# MotorDrivers.net
KiCad netlist of a schematic drawn in Altium Designer
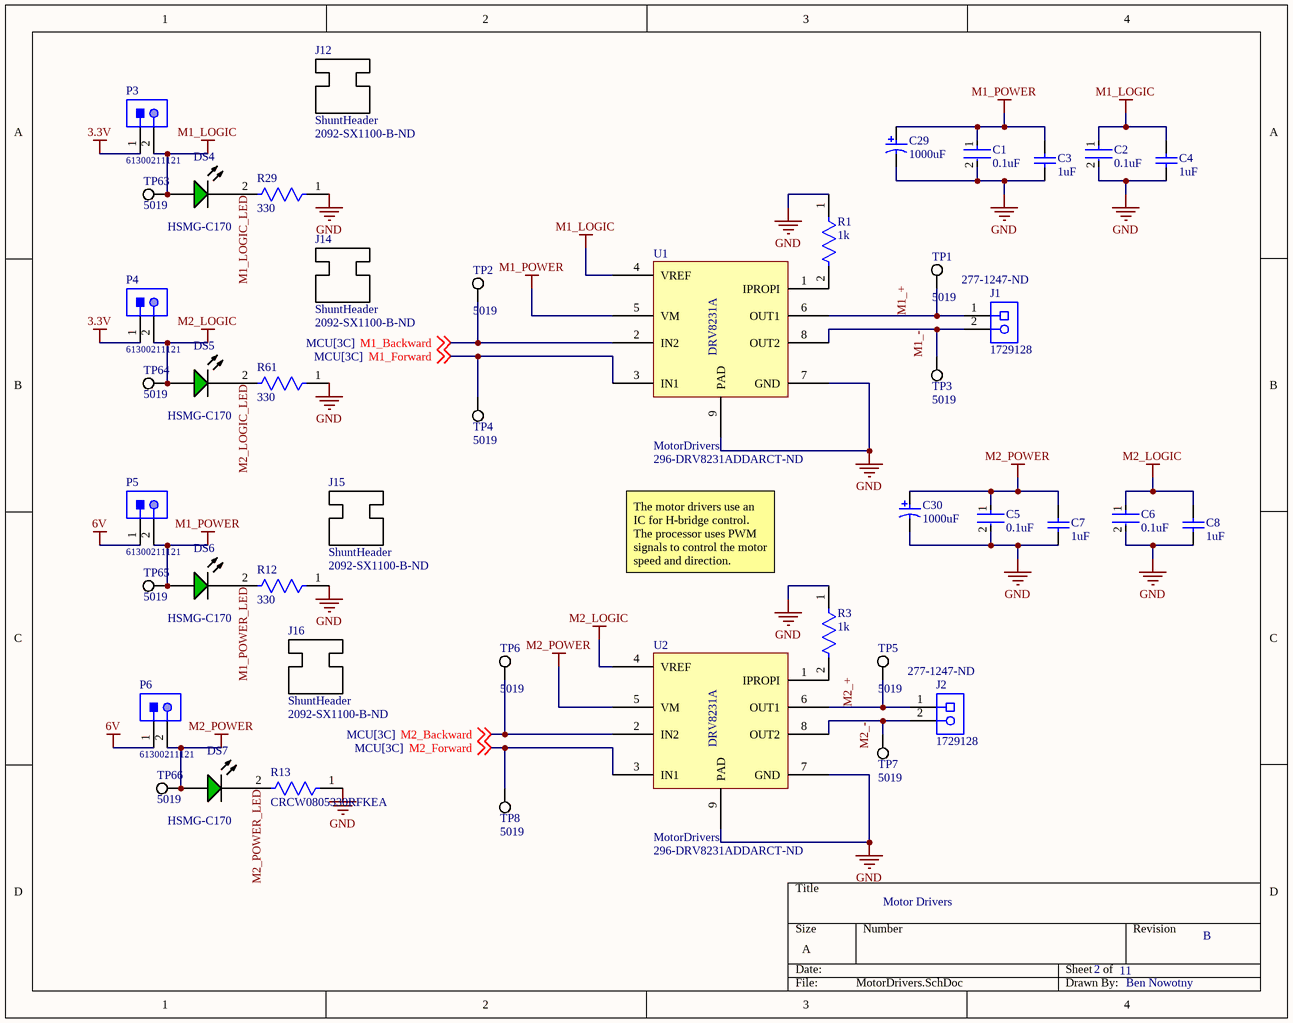
[diagram p0: MotorDrivers.SchDoc]

(export (version "E")
  (design (tool "Eeschema 10.0.6"))
  (components
    (comp (ref "C1")
      (value "0.1uF")
      (footprint "FP-CC0805-0_85-MFG")
      (description "CAP CER 0.1UF 25V X7R 0805")
      (fields (field (name "MANUFACTURER PART NUMBER") "CC0805KRX7R8BB104") (field (name "TOLERANCE") "0.1"))
      (libsource (lib "Altium Content Vault") (part "11868f565c42a9108669ba33697ecf6"))
    )
    (comp (ref "C2")
      (value "0.1uF")
      (footprint "FP-CC0805-0_85-MFG")
      (description "CAP CER 0.1UF 25V X7R 0805")
      (fields (field (name "MANUFACTURER PART NUMBER") "CC0805KRX7R8BB104") (field (name "TOLERANCE") "0.1"))
      (libsource (lib "Altium Content Vault") (part "11868f565c42a9108669ba33697ecf6"))
    )
    (comp (ref "C3")
      (value "1uF")
      (footprint "CAPC2013X145X50ML20T25")
      (fields
        (field (name "PART NUMBER") "CC0805ZRY5V8BB105")
        (field (name "MANUFACTURER") "Yageo")
        (field (name "TOLERANCE") "80%")
      )
      (libsource (lib "Altium Content Vault") (part "CAP"))
    )
    (comp (ref "C4")
      (value "1uF")
      (footprint "CAPC2013X145X50ML20T25")
      (fields
        (field (name "PART NUMBER") "CC0805ZRY5V8BB105")
        (field (name "MANUFACTURER") "Yageo")
        (field (name "TOLERANCE") "80%")
      )
      (libsource (lib "Altium Content Vault") (part "CAP"))
    )
    (comp (ref "C5")
      (value "0.1uF")
      (footprint "FP-CC0805-0_85-MFG")
      (description "CAP CER 0.1UF 25V X7R 0805")
      (fields (field (name "MANUFACTURER PART NUMBER") "CC0805KRX7R8BB104") (field (name "TOLERANCE") "0.1"))
      (libsource (lib "Altium Content Vault") (part "11868f565c42a9108669ba33697ecf6"))
    )
    (comp (ref "C6")
      (value "0.1uF")
      (footprint "FP-CC0805-0_85-MFG")
      (description "CAP CER 0.1UF 25V X7R 0805")
      (fields (field (name "MANUFACTURER PART NUMBER") "CC0805KRX7R8BB104") (field (name "TOLERANCE") "0.1"))
      (libsource (lib "Altium Content Vault") (part "11868f565c42a9108669ba33697ecf6"))
    )
    (comp (ref "C7")
      (value "1uF")
      (footprint "CAPC2013X145X50ML20T25")
      (fields
        (field (name "PART NUMBER") "CC0805ZRY5V8BB105")
        (field (name "MANUFACTURER") "Yageo")
        (field (name "TOLERANCE") "80%")
      )
      (libsource (lib "Altium Content Vault") (part "CAP"))
    )
    (comp (ref "C8")
      (value "1uF")
      (footprint "CAPC2013X145X50ML20T25")
      (fields
        (field (name "PART NUMBER") "CC0805ZRY5V8BB105")
        (field (name "MANUFACTURER") "Yageo")
        (field (name "TOLERANCE") "80%")
      )
      (libsource (lib "Altium Content Vault") (part "CAP"))
    )
    (comp (ref "C29")
      (value "1000uF")
      (footprint "NIC-CAPA2-10X10_V")
      (fields
        (field (name "MANUFACTURER") "Nichicon")
        (field (name "PARTNUMBER") "UUD1A102MNL1GS")
        (field (name "TOLERANCE") "20%")
      )
      (libsource (lib "Altium Content Vault") (part "NIC-CAP-P-2"))
    )
    (comp (ref "C30")
      (value "1000uF")
      (footprint "NIC-CAPA2-10X10_V")
      (fields
        (field (name "MANUFACTURER") "Nichicon")
        (field (name "PARTNUMBER") "UUD1A102MNL1GS")
        (field (name "TOLERANCE") "20%")
      )
      (libsource (lib "Altium Content Vault") (part "NIC-CAP-P-2"))
    )
    (comp (ref "DS4")
      (value "HSMG-C170")
      (footprint "AVAG-HSMX-C170_V")
      (description "Chip LED, Green, 2.2 V, -40 to 85 degC, 2-Pin SMD, Pb-Free, Tape and Reel")
      (fields (field (name "MANUFACTURER") "Avago"))
      (libsource (lib "Altium Content Vault") (part "LED_GREEN_A1K2-2"))
    )
    (comp (ref "DS5")
      (value "HSMG-C170")
      (footprint "AVAG-HSMX-C170_V")
      (description "Chip LED, Green, 2.2 V, -40 to 85 degC, 2-Pin SMD, Pb-Free, Tape and Reel")
      (fields (field (name "MANUFACTURER") "Avago"))
      (libsource (lib "Altium Content Vault") (part "LED_GREEN_A1K2-2"))
    )
    (comp (ref "DS6")
      (value "HSMG-C170")
      (footprint "AVAG-HSMX-C170_V")
      (description "Chip LED, Green, 2.2 V, -40 to 85 degC, 2-Pin SMD, Pb-Free, Tape and Reel")
      (fields (field (name "MANUFACTURER") "Avago"))
      (libsource (lib "Altium Content Vault") (part "LED_GREEN_A1K2-2"))
    )
    (comp (ref "DS7")
      (value "HSMG-C170")
      (footprint "AVAG-HSMX-C170_V")
      (description "Chip LED, Green, 2.2 V, -40 to 85 degC, 2-Pin SMD, Pb-Free, Tape and Reel")
      (fields (field (name "MANUFACTURER") "Avago"))
      (libsource (lib "Altium Content Vault") (part "LED_GREEN_A1K2-2"))
    )
    (comp (ref "J1")
      (value "1729128")
      (footprint "PHOE-1729128-2_V")
      (description "PCB Terminal Block, 13.5 A, 400 V, 2-Pin THD, RoHS, Bulk")
      (fields
        (field (name "MANUFACTURER") "Phoenix Contact")
        (field (name "SUPPLIER PART NUMBER 1") "277-1247-ND")
        (field (name "VOLTAGE") "300V")
      )
      (libsource (lib "Altium Content Vault") (part "CN-2P-F-R2"))
    )
    (comp (ref "J2")
      (value "1729128")
      (footprint "PHOE-1729128-2_V")
      (description "PCB Terminal Block, 13.5 A, 400 V, 2-Pin THD, RoHS, Bulk")
      (fields
        (field (name "MANUFACTURER") "Phoenix Contact")
        (field (name "SUPPLIER PART NUMBER 1") "277-1247-ND")
        (field (name "VOLTAGE") "300V")
      )
      (libsource (lib "Altium Content Vault") (part "CN-2P-F-R2"))
    )
    (comp (ref "J12")
      (value "ShuntHeader")
      (description "Conn Mini Shunt 2 POS 2.54mm Black Cable Mount")
      (fields
        (field (name "MANUFACTURER") "Kycon")
        (field (name "MANUFACTURER PART NUMBER") "SX1100-B")
        (field (name "SUPPLIER PART NUMBER 1") "2092-SX1100-B-ND")
      )
      (libsource (lib "CustomSchematics") (part "ShuntHeader"))
    )
    (comp (ref "J14")
      (value "ShuntHeader")
      (description "Conn Mini Shunt 2 POS 2.54mm Black Cable Mount")
      (fields
        (field (name "MANUFACTURER") "Kycon")
        (field (name "MANUFACTURER PART NUMBER") "SX1100-B")
        (field (name "SUPPLIER PART NUMBER 1") "2092-SX1100-B-ND")
      )
      (libsource (lib "CustomSchematics") (part "ShuntHeader"))
    )
    (comp (ref "J15")
      (value "ShuntHeader")
      (description "Conn Mini Shunt 2 POS 2.54mm Black Cable Mount")
      (fields
        (field (name "MANUFACTURER") "Kycon")
        (field (name "MANUFACTURER PART NUMBER") "SX1100-B")
        (field (name "SUPPLIER PART NUMBER 1") "2092-SX1100-B-ND")
      )
      (libsource (lib "CustomSchematics") (part "ShuntHeader"))
    )
    (comp (ref "J16")
      (value "ShuntHeader")
      (description "Conn Mini Shunt 2 POS 2.54mm Black Cable Mount")
      (fields
        (field (name "MANUFACTURER") "Kycon")
        (field (name "MANUFACTURER PART NUMBER") "SX1100-B")
        (field (name "SUPPLIER PART NUMBER 1") "2092-SX1100-B-ND")
      )
      (libsource (lib "CustomSchematics") (part "ShuntHeader"))
    )
    (comp (ref "P3")
      (value "61300211121")
      (footprint "61300211121")
      (description "THT Vertical Pin Header WR-PHD, Pitch 2.54 mm, Single Row, 2 pins")
      (fields (field (name "MANUFACTURER") "Wurth Elektronik") (field (name "PUBLISHER") "WurthElektronik"))
      (libsource (lib "Altium Content Vault") (part "WE-CN-1P-M-R2"))
    )
    (comp (ref "P4")
      (value "61300211121")
      (footprint "61300211121")
      (description "THT Vertical Pin Header WR-PHD, Pitch 2.54 mm, Single Row, 2 pins")
      (fields (field (name "MANUFACTURER") "Wurth Elektronik") (field (name "PUBLISHER") "WurthElektronik"))
      (libsource (lib "Altium Content Vault") (part "WE-CN-1P-M-R2"))
    )
    (comp (ref "P5")
      (value "61300211121")
      (footprint "61300211121")
      (description "THT Vertical Pin Header WR-PHD, Pitch 2.54 mm, Single Row, 2 pins")
      (fields (field (name "MANUFACTURER") "Wurth Elektronik") (field (name "PUBLISHER") "WurthElektronik"))
      (libsource (lib "Altium Content Vault") (part "WE-CN-1P-M-R2"))
    )
    (comp (ref "P6")
      (value "61300211121")
      (footprint "61300211121")
      (description "THT Vertical Pin Header WR-PHD, Pitch 2.54 mm, Single Row, 2 pins")
      (fields (field (name "MANUFACTURER") "Wurth Elektronik") (field (name "PUBLISHER") "WurthElektronik"))
      (libsource (lib "Altium Content Vault") (part "WE-CN-1P-M-R2"))
    )
    (comp (ref "R1")
      (value "1k")
      (footprint "FP-ERA6A-IPC_C")
      (description "RES 1K OHM 0.1% 1/8W 0805")
      (fields (field (name "TOLERANCE") "0.1%"))
      (libsource (lib "Altium Content Vault") (part "1029c3af85768c4190bb7ad29bc67b5"))
    )
    (comp (ref "R3")
      (value "1k")
      (footprint "FP-ERA6A-IPC_C")
      (description "RES 1K OHM 0.1% 1/8W 0805")
      (fields (field (name "TOLERANCE") "0.1%"))
      (libsource (lib "Altium Content Vault") (part "1029c3af85768c4190bb7ad29bc67b5"))
    )
    (comp (ref "R12")
      (value "330")
      (footprint "FP-CRCW0805-e3-MFG")
      (description "RES Thick Film, 330Ω, 1%, 0.125W, 100ppm/°C, 0805")
      (fields (field (name "TOLERANCE") "1%") (field (name "MANUFACTURER") "Vishay"))
      (libsource (lib "Altium Content Vault") (part "1029c3af85768c4190bb7ad29bc67b5"))
    )
    (comp (ref "R13")
      (value "CRCW0805330RFKEA")
      (footprint "FP-CRCW0805-e3-MFG")
      (description "RES Thick Film, 330Ω, 1%, 0.125W, 100ppm/°C, 0805")
      (fields (field (name "TOLERANCE") "1%"))
      (libsource (lib "Altium Content Vault") (part "1029c3af85768c4190bb7ad29bc67b5"))
    )
    (comp (ref "R29")
      (value "330")
      (footprint "FP-CRCW0805-e3-MFG")
      (description "RES Thick Film, 330Ω, 1%, 0.125W, 100ppm/°C, 0805")
      (fields (field (name "TOLERANCE") "1%") (field (name "MANUFACTURER") "Vishay"))
      (libsource (lib "Altium Content Vault") (part "1029c3af85768c4190bb7ad29bc67b5"))
    )
    (comp (ref "R61")
      (value "330")
      (footprint "FP-CRCW0805-e3-MFG")
      (description "RES Thick Film, 330Ω, 1%, 0.125W, 100ppm/°C, 0805")
      (fields (field (name "TOLERANCE") "1%") (field (name "MANUFACTURER") "Vishay"))
      (libsource (lib "Altium Content Vault") (part "1029c3af85768c4190bb7ad29bc67b5"))
    )
    (comp (ref "TP1")
      (value "5019")
      (footprint "KSTN-5019_V")
      (description "Test Point, 1 Position SMD, RoHS, Tape and Reel")
      (fields (field (name "MANUFACTURER") "Keystone Electronics"))
      (libsource (lib "Altium Content Vault") (part "TESTPOINT_WHITE"))
    )
    (comp (ref "TP2")
      (value "5019")
      (footprint "KSTN-5019_V")
      (description "Test Point, 1 Position SMD, RoHS, Tape and Reel")
      (fields (field (name "MANUFACTURER") "Keystone Electronics"))
      (libsource (lib "Altium Content Vault") (part "TESTPOINT_WHITE"))
    )
    (comp (ref "TP3")
      (value "5019")
      (footprint "KSTN-5019_V")
      (description "Test Point, 1 Position SMD, RoHS, Tape and Reel")
      (fields (field (name "MANUFACTURER") "Keystone Electronics"))
      (libsource (lib "Altium Content Vault") (part "TESTPOINT_WHITE"))
    )
    (comp (ref "TP4")
      (value "5019")
      (footprint "KSTN-5019_V")
      (description "Test Point, 1 Position SMD, RoHS, Tape and Reel")
      (fields (field (name "MANUFACTURER") "Keystone Electronics"))
      (libsource (lib "Altium Content Vault") (part "TESTPOINT_WHITE"))
    )
    (comp (ref "TP5")
      (value "5019")
      (footprint "KSTN-5019_V")
      (description "Test Point, 1 Position SMD, RoHS, Tape and Reel")
      (fields (field (name "MANUFACTURER") "Keystone Electronics"))
      (libsource (lib "Altium Content Vault") (part "TESTPOINT_WHITE"))
    )
    (comp (ref "TP6")
      (value "5019")
      (footprint "KSTN-5019_V")
      (description "Test Point, 1 Position SMD, RoHS, Tape and Reel")
      (fields (field (name "MANUFACTURER") "Keystone Electronics"))
      (libsource (lib "Altium Content Vault") (part "TESTPOINT_WHITE"))
    )
    (comp (ref "TP7")
      (value "5019")
      (footprint "KSTN-5019_V")
      (description "Test Point, 1 Position SMD, RoHS, Tape and Reel")
      (fields (field (name "MANUFACTURER") "Keystone Electronics"))
      (libsource (lib "Altium Content Vault") (part "TESTPOINT_WHITE"))
    )
    (comp (ref "TP8")
      (value "5019")
      (footprint "KSTN-5019_V")
      (description "Test Point, 1 Position SMD, RoHS, Tape and Reel")
      (fields (field (name "MANUFACTURER") "Keystone Electronics"))
      (libsource (lib "Altium Content Vault") (part "TESTPOINT_WHITE"))
    )
    (comp (ref "TP63")
      (value "5019")
      (footprint "KSTN-5019_V")
      (description "Test Point, 1 Position SMD, RoHS, Tape and Reel")
      (fields (field (name "MANUFACTURER") "Keystone Electronics"))
      (libsource (lib "Altium Content Vault") (part "TESTPOINT_WHITE"))
    )
    (comp (ref "TP64")
      (value "5019")
      (footprint "KSTN-5019_V")
      (description "Test Point, 1 Position SMD, RoHS, Tape and Reel")
      (fields (field (name "MANUFACTURER") "Keystone Electronics"))
      (libsource (lib "Altium Content Vault") (part "TESTPOINT_WHITE"))
    )
    (comp (ref "TP65")
      (value "5019")
      (footprint "KSTN-5019_V")
      (description "Test Point, 1 Position SMD, RoHS, Tape and Reel")
      (fields (field (name "MANUFACTURER") "Keystone Electronics"))
      (libsource (lib "Altium Content Vault") (part "TESTPOINT_WHITE"))
    )
    (comp (ref "TP66")
      (value "5019")
      (footprint "KSTN-5019_V")
      (description "Test Point, 1 Position SMD, RoHS, Tape and Reel")
      (fields (field (name "MANUFACTURER") "Keystone Electronics"))
      (libsource (lib "Altium Content Vault") (part "TESTPOINT_WHITE"))
    )
    (comp (ref "U1")
      (value "MotorDrivers")
      (footprint "SOIC127P600X170_HS-9N")
      (fields
        (field (name "MANUFACTURER") "Texas Instruments")
        (field (name "MANUFACTURER PART NUMBER") "DRV8231ADDAR")
        (field (name "SUPPLIER PART NUMBER 1") "296-DRV8231ADDARCT-ND")
      )
      (libsource (lib "CustomSchematics") (part "MotorDrivers"))
    )
    (comp (ref "U2")
      (value "MotorDrivers")
      (footprint "SOIC127P600X170_HS-9N")
      (fields
        (field (name "MANUFACTURER") "Texas Instruments")
        (field (name "MANUFACTURER PART NUMBER") "DRV8231ADDAR")
        (field (name "SUPPLIER PART NUMBER 1") "296-DRV8231ADDARCT-ND")
      )
      (libsource (lib "CustomSchematics") (part "MotorDrivers"))
    )
  )
  (nets
    (net (code "1") (name "/M1_+") (class "Default")
      (node (ref "J1") (pin "1") (pinfunction "1_1") (pintype "passive"))
      (node (ref "TP1") (pin "1") (pinfunction "1_1") (pintype "passive"))
      (node (ref "U1") (pin "6") (pinfunction "OUT1_6") (pintype "passive"))
    )
    (net (code "2") (name "/M1_-") (class "Default")
      (node (ref "J1") (pin "2") (pinfunction "2_2") (pintype "passive"))
      (node (ref "TP3") (pin "1") (pinfunction "1_1") (pintype "passive"))
      (node (ref "U1") (pin "8") (pinfunction "OUT2_8") (pintype "passive"))
    )
    (net (code "3") (name "/M1_LOGIC_LED") (class "Default")
      (node (ref "DS4") (pin "2") (pinfunction "K_2") (pintype "passive"))
      (node (ref "R29") (pin "2") (pinfunction "2_2") (pintype "passive"))
    )
    (net (code "4") (name "/M1_POWER_LED") (class "Default")
      (node (ref "DS6") (pin "2") (pinfunction "K_2") (pintype "passive"))
      (node (ref "R12") (pin "2") (pinfunction "2_2") (pintype "passive"))
    )
    (net (code "5") (name "/M2_+") (class "Default")
      (node (ref "J2") (pin "1") (pinfunction "1_1") (pintype "passive"))
      (node (ref "TP5") (pin "1") (pinfunction "1_1") (pintype "passive"))
      (node (ref "U2") (pin "6") (pinfunction "OUT1_6") (pintype "passive"))
    )
    (net (code "6") (name "/M2_-") (class "Default")
      (node (ref "J2") (pin "2") (pinfunction "2_2") (pintype "passive"))
      (node (ref "TP7") (pin "1") (pinfunction "1_1") (pintype "passive"))
      (node (ref "U2") (pin "8") (pinfunction "OUT2_8") (pintype "passive"))
    )
    (net (code "7") (name "/M2_LOGIC_LED") (class "Default")
      (node (ref "DS5") (pin "2") (pinfunction "K_2") (pintype "passive"))
      (node (ref "R61") (pin "2") (pinfunction "2_2") (pintype "passive"))
    )
    (net (code "8") (name "/M2_POWER_LED") (class "Default")
      (node (ref "DS7") (pin "2") (pinfunction "K_2") (pintype "passive"))
      (node (ref "R13") (pin "2") (pinfunction "2_2") (pintype "passive"))
    )
    (net (code "9") (name "3.3V") (class "Default")
      (node (ref "P3") (pin "1") (pinfunction "1_1") (pintype "passive"))
      (node (ref "P4") (pin "1") (pinfunction "1_1") (pintype "passive"))
    )
    (net (code "10") (name "6V") (class "Default")
      (node (ref "P5") (pin "1") (pinfunction "1_1") (pintype "passive"))
      (node (ref "P6") (pin "1") (pinfunction "1_1") (pintype "passive"))
    )
    (net (code "11") (name "GND") (class "Default")
      (node (ref "C1") (pin "2") (pinfunction "2_2") (pintype "passive"))
      (node (ref "C2") (pin "2") (pinfunction "2_2") (pintype "passive"))
      (node (ref "C29") (pin "2") (pinfunction "2_2") (pintype "passive"))
      (node (ref "C3") (pin "1") (pinfunction "1_1") (pintype "passive"))
      (node (ref "C30") (pin "2") (pinfunction "2_2") (pintype "passive"))
      (node (ref "C4") (pin "1") (pinfunction "1_1") (pintype "passive"))
      (node (ref "C5") (pin "2") (pinfunction "2_2") (pintype "passive"))
      (node (ref "C6") (pin "2") (pinfunction "2_2") (pintype "passive"))
      (node (ref "C7") (pin "1") (pinfunction "1_1") (pintype "passive"))
      (node (ref "C8") (pin "1") (pinfunction "1_1") (pintype "passive"))
      (node (ref "R1") (pin "1") (pinfunction "1_1") (pintype "passive"))
      (node (ref "R12") (pin "1") (pinfunction "1_1") (pintype "passive"))
      (node (ref "R13") (pin "1") (pinfunction "1_1") (pintype "passive"))
      (node (ref "R29") (pin "1") (pinfunction "1_1") (pintype "passive"))
      (node (ref "R3") (pin "1") (pinfunction "1_1") (pintype "passive"))
      (node (ref "R61") (pin "1") (pinfunction "1_1") (pintype "passive"))
      (node (ref "U1") (pin "7") (pinfunction "GND_7") (pintype "passive"))
      (node (ref "U1") (pin "9") (pinfunction "PAD_9") (pintype "passive"))
      (node (ref "U2") (pin "7") (pinfunction "GND_7") (pintype "passive"))
      (node (ref "U2") (pin "9") (pinfunction "PAD_9") (pintype "passive"))
    )
    (net (code "12") (name "M1_Backward") (class "Default")
      (node (ref "TP2") (pin "1") (pinfunction "1_1") (pintype "passive"))
      (node (ref "U1") (pin "2") (pinfunction "IN2_2") (pintype "passive"))
    )
    (net (code "13") (name "M1_Forward") (class "Default")
      (node (ref "TP4") (pin "1") (pinfunction "1_1") (pintype "passive"))
      (node (ref "U1") (pin "3") (pinfunction "IN1_3") (pintype "passive"))
    )
    (net (code "14") (name "M1_LOGIC") (class "Default")
      (node (ref "C2") (pin "1") (pinfunction "1_1") (pintype "passive"))
      (node (ref "C4") (pin "2") (pinfunction "2_2") (pintype "passive"))
      (node (ref "DS4") (pin "1") (pinfunction "A_1") (pintype "passive"))
      (node (ref "P3") (pin "2") (pinfunction "2_2") (pintype "passive"))
      (node (ref "TP63") (pin "1") (pinfunction "1_1") (pintype "passive"))
      (node (ref "U1") (pin "4") (pinfunction "VREF_4") (pintype "passive"))
    )
    (net (code "15") (name "M1_POWER") (class "Default")
      (node (ref "C1") (pin "1") (pinfunction "1_1") (pintype "passive"))
      (node (ref "C29") (pin "1") (pinfunction "1_1") (pintype "passive"))
      (node (ref "C3") (pin "2") (pinfunction "2_2") (pintype "passive"))
      (node (ref "DS6") (pin "1") (pinfunction "A_1") (pintype "passive"))
      (node (ref "P5") (pin "2") (pinfunction "2_2") (pintype "passive"))
      (node (ref "TP65") (pin "1") (pinfunction "1_1") (pintype "passive"))
      (node (ref "U1") (pin "5") (pinfunction "VM_5") (pintype "passive"))
    )
    (net (code "16") (name "M2_Backward") (class "Default")
      (node (ref "TP6") (pin "1") (pinfunction "1_1") (pintype "passive"))
      (node (ref "U2") (pin "2") (pinfunction "IN2_2") (pintype "passive"))
    )
    (net (code "17") (name "M2_Forward") (class "Default")
      (node (ref "TP8") (pin "1") (pinfunction "1_1") (pintype "passive"))
      (node (ref "U2") (pin "3") (pinfunction "IN1_3") (pintype "passive"))
    )
    (net (code "18") (name "M2_LOGIC") (class "Default")
      (node (ref "C6") (pin "1") (pinfunction "1_1") (pintype "passive"))
      (node (ref "C8") (pin "2") (pinfunction "2_2") (pintype "passive"))
      (node (ref "DS5") (pin "1") (pinfunction "A_1") (pintype "passive"))
      (node (ref "P4") (pin "2") (pinfunction "2_2") (pintype "passive"))
      (node (ref "TP64") (pin "1") (pinfunction "1_1") (pintype "passive"))
      (node (ref "U2") (pin "4") (pinfunction "VREF_4") (pintype "passive"))
    )
    (net (code "19") (name "M2_POWER") (class "Default")
      (node (ref "C30") (pin "1") (pinfunction "1_1") (pintype "passive"))
      (node (ref "C5") (pin "1") (pinfunction "1_1") (pintype "passive"))
      (node (ref "C7") (pin "2") (pinfunction "2_2") (pintype "passive"))
      (node (ref "DS7") (pin "1") (pinfunction "A_1") (pintype "passive"))
      (node (ref "P6") (pin "2") (pinfunction "2_2") (pintype "passive"))
      (node (ref "TP66") (pin "1") (pinfunction "1_1") (pintype "passive"))
      (node (ref "U2") (pin "5") (pinfunction "VM_5") (pintype "passive"))
    )
    (net (code "20") (name "Net-(U1-IPROPI)") (class "Default")
      (node (ref "R1") (pin "2") (pinfunction "2_2") (pintype "passive"))
      (node (ref "U1") (pin "1") (pinfunction "IPROPI_1") (pintype "passive"))
    )
    (net (code "21") (name "Net-(U2-IPROPI)") (class "Default")
      (node (ref "R3") (pin "2") (pinfunction "2_2") (pintype "passive"))
      (node (ref "U2") (pin "1") (pinfunction "IPROPI_1") (pintype "passive"))
    )
  )
)
